# Headers.net
KiCad netlist of a schematic drawn in Altium Designer
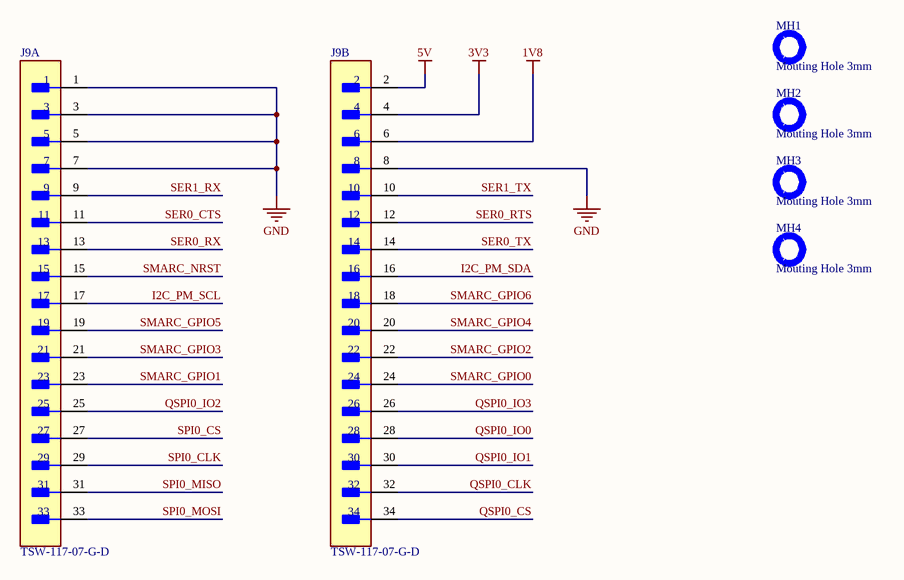
[diagram p0: Headers.SchDoc]

(export (version "E")
  (design (tool "Eeschema 10.0.6"))
  (components
    (comp (ref "J9")
      (value "TSW-117-07-G-D")
      (footprint "FP-TSW-117-07-G-D-MFG")
      (description "CONN HEADER VERT 34POS 2.54MM")
      (fields
        (field (name "MANUFACTURER") "Samtec")
        (field (name "OCTOPART") "https://octopart.com/tsw-117-07-g-d-samtec-272162")
      )
      (libsource (lib "Altium Content Vault") (part "2eb0580c3bcb72051dcde2e0bc23fb0"))
    )
    (comp (ref "MH1") (value "Mouting Hole 3mm") (footprint "MH3") (libsource (lib "Master") (part "MH3")))
    (comp (ref "MH2") (value "Mouting Hole 3mm") (footprint "MH3") (libsource (lib "Master") (part "MH3")))
    (comp (ref "MH3") (value "Mouting Hole 3mm") (footprint "MH3") (libsource (lib "Master") (part "MH3")))
    (comp (ref "MH4") (value "Mouting Hole 3mm") (footprint "MH3") (libsource (lib "Master") (part "MH3")))
  )
  (nets
    (net (code "1") (name "/I2C_PM_SCL") (class "Default")
      (node (ref "J9") (pin "17") (pinfunction "17_17") (pintype "passive"))
    )
    (net (code "2") (name "/I2C_PM_SDA") (class "Default")
      (node (ref "J9") (pin "16") (pinfunction "16_16") (pintype "passive"))
    )
    (net (code "3") (name "/QSPI0_CLK") (class "Default")
      (node (ref "J9") (pin "32") (pinfunction "32_32") (pintype "passive"))
    )
    (net (code "4") (name "/QSPI0_CS") (class "Default")
      (node (ref "J9") (pin "34") (pinfunction "34_34") (pintype "passive"))
    )
    (net (code "5") (name "/QSPI0_IO0") (class "Default")
      (node (ref "J9") (pin "28") (pinfunction "28_28") (pintype "passive"))
    )
    (net (code "6") (name "/QSPI0_IO1") (class "Default")
      (node (ref "J9") (pin "30") (pinfunction "30_30") (pintype "passive"))
    )
    (net (code "7") (name "/QSPI0_IO2") (class "Default")
      (node (ref "J9") (pin "25") (pinfunction "25_25") (pintype "passive"))
    )
    (net (code "8") (name "/QSPI0_IO3") (class "Default")
      (node (ref "J9") (pin "26") (pinfunction "26_26") (pintype "passive"))
    )
    (net (code "9") (name "/SER0_CTS") (class "Default")
      (node (ref "J9") (pin "11") (pinfunction "11_11") (pintype "passive"))
    )
    (net (code "10") (name "/SER0_RTS") (class "Default")
      (node (ref "J9") (pin "12") (pinfunction "12_12") (pintype "passive"))
    )
    (net (code "11") (name "/SER0_RX") (class "Default")
      (node (ref "J9") (pin "13") (pinfunction "13_13") (pintype "passive"))
    )
    (net (code "12") (name "/SER0_TX") (class "Default")
      (node (ref "J9") (pin "14") (pinfunction "14_14") (pintype "passive"))
    )
    (net (code "13") (name "/SER1_RX") (class "Default")
      (node (ref "J9") (pin "9") (pinfunction "9_9") (pintype "passive"))
    )
    (net (code "14") (name "/SER1_TX") (class "Default")
      (node (ref "J9") (pin "10") (pinfunction "10_10") (pintype "passive"))
    )
    (net (code "15") (name "/SMARC_GPIO0") (class "Default")
      (node (ref "J9") (pin "24") (pinfunction "24_24") (pintype "passive"))
    )
    (net (code "16") (name "/SMARC_GPIO1") (class "Default")
      (node (ref "J9") (pin "23") (pinfunction "23_23") (pintype "passive"))
    )
    (net (code "17") (name "/SMARC_GPIO2") (class "Default")
      (node (ref "J9") (pin "22") (pinfunction "22_22") (pintype "passive"))
    )
    (net (code "18") (name "/SMARC_GPIO3") (class "Default")
      (node (ref "J9") (pin "21") (pinfunction "21_21") (pintype "passive"))
    )
    (net (code "19") (name "/SMARC_GPIO4") (class "Default")
      (node (ref "J9") (pin "20") (pinfunction "20_20") (pintype "passive"))
    )
    (net (code "20") (name "/SMARC_GPIO5") (class "Default")
      (node (ref "J9") (pin "19") (pinfunction "19_19") (pintype "passive"))
    )
    (net (code "21") (name "/SMARC_GPIO6") (class "Default")
      (node (ref "J9") (pin "18") (pinfunction "18_18") (pintype "passive"))
    )
    (net (code "22") (name "/SMARC_NRST") (class "Default")
      (node (ref "J9") (pin "15") (pinfunction "15_15") (pintype "passive"))
    )
    (net (code "23") (name "/SPI0_CLK") (class "Default")
      (node (ref "J9") (pin "29") (pinfunction "29_29") (pintype "passive"))
    )
    (net (code "24") (name "/SPI0_CS") (class "Default")
      (node (ref "J9") (pin "27") (pinfunction "27_27") (pintype "passive"))
    )
    (net (code "25") (name "/SPI0_MISO") (class "Default")
      (node (ref "J9") (pin "31") (pinfunction "31_31") (pintype "passive"))
    )
    (net (code "26") (name "/SPI0_MOSI") (class "Default")
      (node (ref "J9") (pin "33") (pinfunction "33_33") (pintype "passive"))
    )
    (net (code "27") (name "1V8") (class "Default")
      (node (ref "J9") (pin "6") (pinfunction "6_6") (pintype "passive"))
    )
    (net (code "28") (name "3V3") (class "Default")
      (node (ref "J9") (pin "4") (pinfunction "4_4") (pintype "passive"))
    )
    (net (code "29") (name "5V") (class "Default")
      (node (ref "J9") (pin "2") (pinfunction "2_2") (pintype "passive"))
    )
    (net (code "30") (name "GND") (class "Default")
      (node (ref "J9") (pin "1") (pinfunction "1_1") (pintype "passive"))
      (node (ref "J9") (pin "3") (pinfunction "3_3") (pintype "passive"))
      (node (ref "J9") (pin "5") (pinfunction "5_5") (pintype "passive"))
      (node (ref "J9") (pin "7") (pinfunction "7_7") (pintype "passive"))
      (node (ref "J9") (pin "8") (pinfunction "8_8") (pintype "passive"))
    )
  )
)
